# Sheet1.net
KiCad netlist of a schematic drawn in Altium Designer
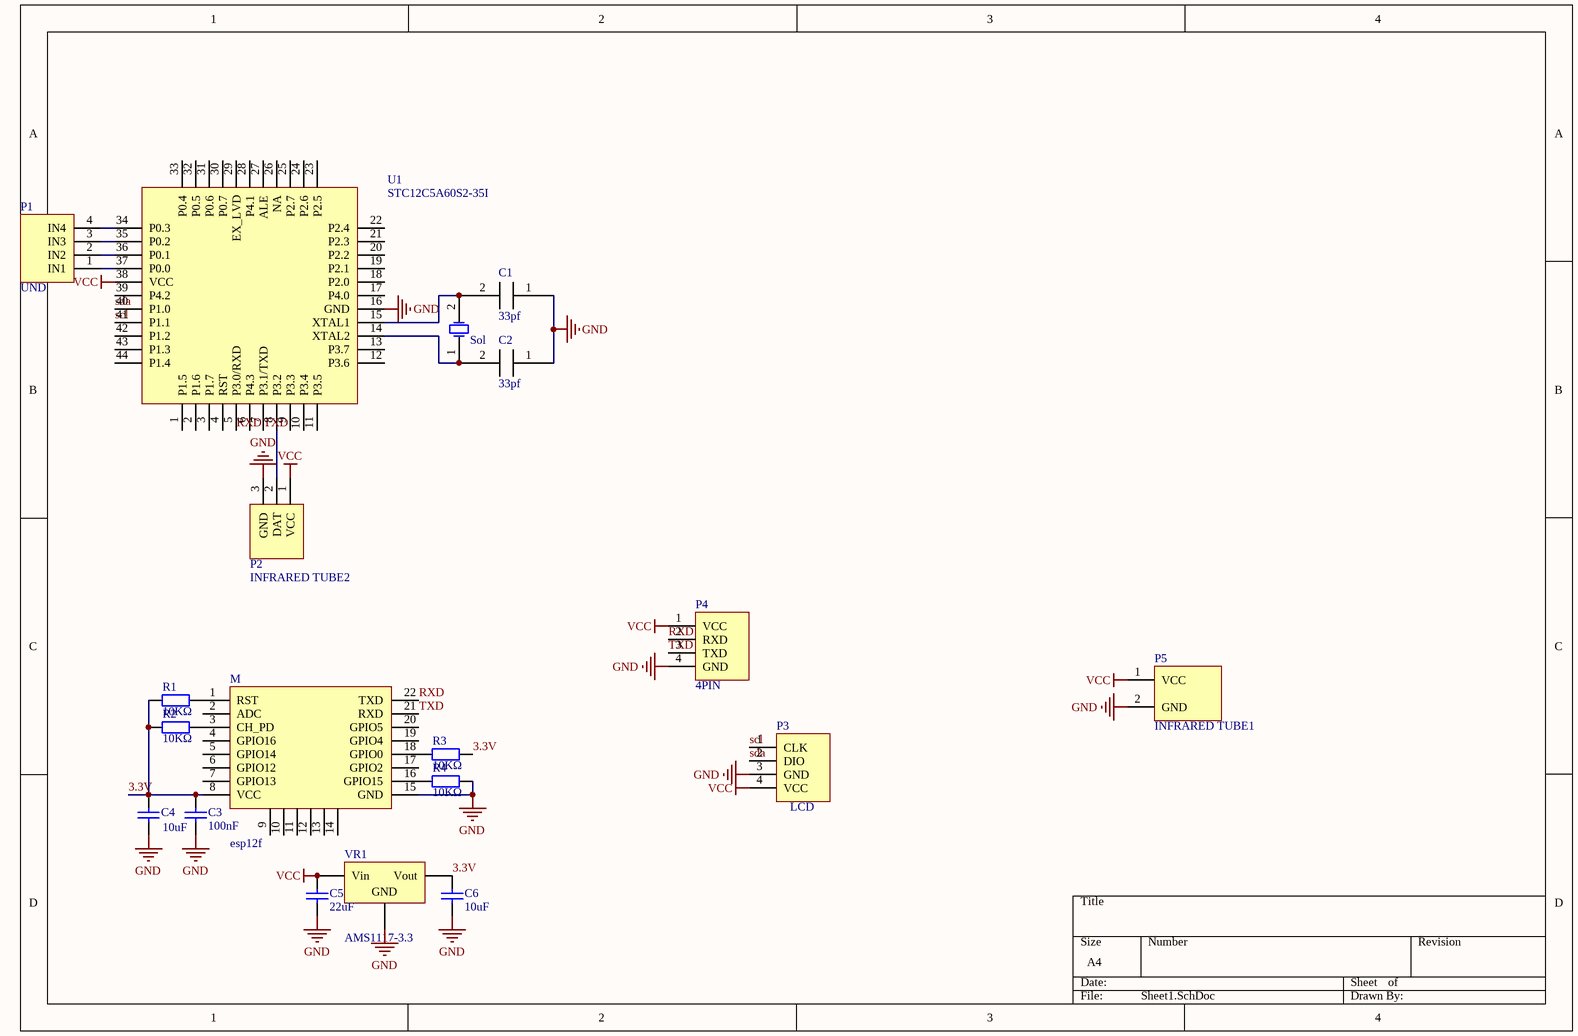
[diagram p0: Sheet1.SchDoc]

(export (version "E")
  (design (tool "Eeschema 10.0.6"))
  (components
    (comp (ref "C1")
      (value "33pf")
      (footprint "C 0805_M")
      (description "电容")
      (libsource (lib "Schlib1") (part "电容"))
    )
    (comp (ref "C2")
      (value "33pf")
      (footprint "C 0805_M")
      (description "电容")
      (libsource (lib "Schlib1") (part "电容"))
    )
    (comp (ref "C3")
      (value "100nF")
      (footprint "0805_C")
      (description "贴片电容")
      (libsource (lib "Cap") (part "0805 100nF(104) 10% 50V"))
    )
    (comp (ref "C4")
      (value "10uF")
      (footprint "0805_C")
      (description "贴片电容")
      (libsource (lib "Cap") (part "0805 10uF (106) 10% 25V"))
    )
    (comp (ref "C5")
      (value "22uF")
      (footprint "0805_C")
      (description "贴片电容")
      (libsource (lib "Cap") (part "0805 100nF(104) 10% 50V"))
    )
    (comp (ref "C6")
      (value "10uF")
      (footprint "0805_C")
      (description "贴片电容")
      (libsource (lib "Cap") (part "0805 100nF(104) 10% 50V"))
    )
    (comp (ref "M") (value "esp12f") (footprint "ESP_12E") (libsource (lib "Schlib1") (part "esp12f")))
    (comp (ref "P1") (value "UND") (footprint "HDR2.54-LI-4P") (libsource (lib "*") (part "4PIN UND")))
    (comp (ref "P2")
      (value "INFRARED TUBE2")
      (footprint "XH2.54-LI-3P")
      (libsource (lib "*") (part "INFRARED TUBE 2"))
    )
    (comp (ref "P3") (value "LCD") (footprint "HDR2.54-M-LI-4P") (libsource (lib "*") (part "lcd")))
    (comp (ref "P4") (value "4PIN") (footprint "HDR2.54-LI-4P") (libsource (lib "*") (part "4PIN")))
    (comp (ref "P5")
      (value "INFRARED TUBE1")
      (footprint "XH2.54-LI-2P")
      (libsource (lib "*") (part "INFRARED TUBE1"))
    )
    (comp (ref "R1")
      (value "10KΩ")
      (footprint "0805_R")
      (description "贴片电阻")
      (libsource (lib "RES") (part "0805 10KΩ (1002) 1%"))
    )
    (comp (ref "R2")
      (value "10KΩ")
      (footprint "0805_R")
      (description "贴片电阻")
      (libsource (lib "RES") (part "0805 10KΩ (1002) 1%"))
    )
    (comp (ref "R3")
      (value "10KΩ")
      (footprint "0805_R")
      (description "贴片电阻")
      (libsource (lib "RES") (part "0805 10KΩ (1002) 1%"))
    )
    (comp (ref "R4")
      (value "10KΩ")
      (footprint "0805_R")
      (description "贴片电阻")
      (libsource (lib "RES") (part "0805 10KΩ (1002) 1%"))
    )
    (comp (ref "Sol")
      (value "CrystalOscillator")
      (footprint "OSC HC-49S")
      (description "晶振")
      (libsource (lib "Schlib1") (part "XTAL"))
    )
    (comp (ref "U1")
      (value "STC12C5A60S2-35I")
      (footprint "LQFP-44_10x10x08P")
      (description "MCU")
      (libsource (lib "Schlib1") (part "STC12C5A60S2-35I"))
    )
    (comp (ref "VR1")
      (value "AMS1117-3.3")
      (footprint "SOT-223")
      (description "低压差线性稳压(LDO)")
      (libsource (lib "LDO") (part "SOT-223 AMS1117-3.3"))
    )
  )
  (nets
    (net (code "1") (name "/3.3V") (class "Default")
      (node (ref "C3") (pin "2") (pinfunction "2_2") (pintype "passive"))
      (node (ref "C4") (pin "2") (pinfunction "2_2") (pintype "passive"))
      (node (ref "C6") (pin "2") (pinfunction "2_2") (pintype "passive"))
      (node (ref "M") (pin "8") (pinfunction "VCC_8") (pintype "passive"))
      (node (ref "R1") (pin "1") (pinfunction "1_1") (pintype "passive"))
      (node (ref "R2") (pin "1") (pinfunction "1_1") (pintype "passive"))
      (node (ref "R3") (pin "2") (pinfunction "2_2") (pintype "passive"))
      (node (ref "VR1") (pin "2") (pinfunction "Vout_2") (pintype "passive"))
    )
    (net (code "2") (name "/RXD") (class "Default")
      (node (ref "M") (pin "22") (pinfunction "TXD_22") (pintype "passive"))
      (node (ref "P4") (pin "2") (pinfunction "RXD_2") (pintype "passive"))
      (node (ref "U1") (pin "5") (pinfunction "P3.0/RXD_5") (pintype "passive"))
    )
    (net (code "3") (name "/TXD") (class "Default")
      (node (ref "M") (pin "21") (pinfunction "RXD_21") (pintype "passive"))
      (node (ref "P4") (pin "3") (pinfunction "TXD_3") (pintype "passive"))
      (node (ref "U1") (pin "7") (pinfunction "P3.1/TXD_7") (pintype "passive"))
    )
    (net (code "4") (name "/scl") (class "Default")
      (node (ref "P3") (pin "1") (pinfunction "CLK_1") (pintype "passive"))
      (node (ref "U1") (pin "41") (pinfunction "P1.1_41") (pintype "passive"))
    )
    (net (code "5") (name "/sda") (class "Default")
      (node (ref "P3") (pin "2") (pinfunction "DIO_2") (pintype "passive"))
      (node (ref "U1") (pin "40") (pinfunction "P1.0_40") (pintype "passive"))
    )
    (net (code "6") (name "GND") (class "Default")
      (node (ref "C1") (pin "1") (pinfunction "1_1") (pintype "passive"))
      (node (ref "C2") (pin "1") (pinfunction "1_1") (pintype "passive"))
      (node (ref "C3") (pin "1") (pinfunction "1_1") (pintype "passive"))
      (node (ref "C4") (pin "1") (pinfunction "1_1") (pintype "passive"))
      (node (ref "C5") (pin "1") (pinfunction "1_1") (pintype "passive"))
      (node (ref "C6") (pin "1") (pinfunction "1_1") (pintype "passive"))
      (node (ref "M") (pin "15") (pinfunction "GND_15") (pintype "passive"))
      (node (ref "P2") (pin "3") (pinfunction "GND_3") (pintype "passive"))
      (node (ref "P3") (pin "3") (pinfunction "GND_3") (pintype "passive"))
      (node (ref "P4") (pin "4") (pinfunction "GND_4") (pintype "passive"))
      (node (ref "P5") (pin "2") (pinfunction "GND_2") (pintype "passive"))
      (node (ref "R4") (pin "2") (pinfunction "2_2") (pintype "passive"))
      (node (ref "U1") (pin "16") (pinfunction "GND_16") (pintype "power_in"))
      (node (ref "VR1") (pin "1") (pinfunction "GND_1") (pintype "passive"))
    )
    (net (code "7") (name "Net-(M-CH_PD)") (class "Default")
      (node (ref "M") (pin "3") (pinfunction "CH_PD_3") (pintype "passive"))
      (node (ref "R2") (pin "2") (pinfunction "2_2") (pintype "passive"))
    )
    (net (code "8") (name "Net-(M-GPIO0)") (class "Default")
      (node (ref "M") (pin "18") (pinfunction "GPIO0_18") (pintype "passive"))
      (node (ref "R3") (pin "1") (pinfunction "1_1") (pintype "passive"))
    )
    (net (code "9") (name "Net-(M-GPIO15)") (class "Default")
      (node (ref "M") (pin "16") (pinfunction "GPIO15_16") (pintype "passive"))
      (node (ref "R4") (pin "1") (pinfunction "1_1") (pintype "passive"))
    )
    (net (code "10") (name "Net-(M-RST)") (class "Default")
      (node (ref "M") (pin "1") (pinfunction "RST_1") (pintype "passive"))
      (node (ref "R1") (pin "2") (pinfunction "2_2") (pintype "passive"))
    )
    (net (code "11") (name "Net-(P1-IN1)") (class "Default")
      (node (ref "P1") (pin "1") (pinfunction "IN1_1") (pintype "passive"))
      (node (ref "U1") (pin "37") (pinfunction "P0.0_37") (pintype "passive"))
    )
    (net (code "12") (name "Net-(P1-IN2)") (class "Default")
      (node (ref "P1") (pin "2") (pinfunction "IN2_2") (pintype "passive"))
      (node (ref "U1") (pin "36") (pinfunction "P0.1_36") (pintype "passive"))
    )
    (net (code "13") (name "Net-(P1-IN3)") (class "Default")
      (node (ref "P1") (pin "3") (pinfunction "IN3_3") (pintype "passive"))
      (node (ref "U1") (pin "35") (pinfunction "P0.2_35") (pintype "passive"))
    )
    (net (code "14") (name "Net-(P1-IN4)") (class "Default")
      (node (ref "P1") (pin "4") (pinfunction "IN4_4") (pintype "passive"))
      (node (ref "U1") (pin "34") (pinfunction "P0.3_34") (pintype "passive"))
    )
    (net (code "15") (name "Net-(P2-DAT)") (class "Default")
      (node (ref "P2") (pin "2") (pinfunction "DAT_2") (pintype "passive"))
      (node (ref "U1") (pin "8") (pinfunction "P3.2_8") (pintype "passive"))
    )
    (net (code "16") (name "Net-(Sol-OSC1)") (class "Default")
      (node (ref "C2") (pin "2") (pinfunction "2_2") (pintype "passive"))
      (node (ref "Sol") (pin "1") (pinfunction "OSC1_1") (pintype "passive"))
      (node (ref "U1") (pin "14") (pinfunction "XTAL2_14") (pintype "passive"))
    )
    (net (code "17") (name "Net-(Sol-OSC2)") (class "Default")
      (node (ref "C1") (pin "2") (pinfunction "2_2") (pintype "passive"))
      (node (ref "Sol") (pin "2") (pinfunction "OSC2_2") (pintype "passive"))
      (node (ref "U1") (pin "15") (pinfunction "XTAL1_15") (pintype "passive"))
    )
    (net (code "18") (name "VCC") (class "Default")
      (node (ref "C5") (pin "2") (pinfunction "2_2") (pintype "passive"))
      (node (ref "P2") (pin "1") (pinfunction "VCC_1") (pintype "passive"))
      (node (ref "P3") (pin "4") (pinfunction "VCC_4") (pintype "passive"))
      (node (ref "P4") (pin "1") (pinfunction "VCC_1") (pintype "passive"))
      (node (ref "P5") (pin "1") (pinfunction "VCC_1") (pintype "passive"))
      (node (ref "U1") (pin "38") (pinfunction "VCC_38") (pintype "power_in"))
      (node (ref "VR1") (pin "3") (pinfunction "Vin_3") (pintype "passive"))
    )
    (net (code "19") (name "unconnected-(M-ADC-Pad2)") (class "Default")
      (node (ref "M") (pin "2") (pinfunction "ADC_2") (pintype "passive"))
    )
    (net (code "20") (name "unconnected-(M-GPIO2-Pad17)") (class "Default")
      (node (ref "M") (pin "17") (pinfunction "GPIO2_17") (pintype "passive"))
    )
    (net (code "21") (name "unconnected-(M-GPIO4-Pad19)") (class "Default")
      (node (ref "M") (pin "19") (pinfunction "GPIO4_19") (pintype "passive"))
    )
    (net (code "22") (name "unconnected-(M-GPIO5-Pad20)") (class "Default")
      (node (ref "M") (pin "20") (pinfunction "GPIO5_20") (pintype "passive"))
    )
    (net (code "23") (name "unconnected-(M-GPIO12-Pad6)") (class "Default")
      (node (ref "M") (pin "6") (pinfunction "GPIO12_6") (pintype "passive"))
    )
    (net (code "24") (name "unconnected-(M-GPIO13-Pad7)") (class "Default")
      (node (ref "M") (pin "7") (pinfunction "GPIO13_7") (pintype "passive"))
    )
    (net (code "25") (name "unconnected-(M-GPIO14-Pad5)") (class "Default")
      (node (ref "M") (pin "5") (pinfunction "GPIO14_5") (pintype "passive"))
    )
    (net (code "26") (name "unconnected-(M-GPIO16-Pad4)") (class "Default")
      (node (ref "M") (pin "4") (pinfunction "GPIO16_4") (pintype "passive"))
    )
    (net (code "27") (name "unconnected-(M-Pad9)") (class "Default")
      (node (ref "M") (pin "9") (pintype "passive"))
    )
    (net (code "28") (name "unconnected-(M-Pad10)") (class "Default")
      (node (ref "M") (pin "10") (pintype "passive"))
    )
    (net (code "29") (name "unconnected-(M-Pad11)") (class "Default")
      (node (ref "M") (pin "11") (pintype "passive"))
    )
    (net (code "30") (name "unconnected-(M-Pad12)") (class "Default")
      (node (ref "M") (pin "12") (pintype "passive"))
    )
    (net (code "31") (name "unconnected-(M-Pad13)") (class "Default")
      (node (ref "M") (pin "13") (pintype "passive"))
    )
    (net (code "32") (name "unconnected-(M-Pad14)") (class "Default")
      (node (ref "M") (pin "14") (pintype "passive"))
    )
    (net (code "33") (name "unconnected-(U1-ALE-Pad27)") (class "Default")
      (node (ref "U1") (pin "27") (pinfunction "ALE_27") (pintype "passive"))
    )
    (net (code "34") (name "unconnected-(U1-EX_LVD-Pad29)") (class "Default")
      (node (ref "U1") (pin "29") (pinfunction "EX_LVD_29") (pintype "passive"))
    )
    (net (code "35") (name "unconnected-(U1-NA-Pad26)") (class "Default")
      (node (ref "U1") (pin "26") (pinfunction "NA_26") (pintype "passive"))
    )
    (net (code "36") (name "unconnected-(U1-P0.4-Pad33)") (class "Default")
      (node (ref "U1") (pin "33") (pinfunction "P0.4_33") (pintype "passive"))
    )
    (net (code "37") (name "unconnected-(U1-P0.5-Pad32)") (class "Default")
      (node (ref "U1") (pin "32") (pinfunction "P0.5_32") (pintype "passive"))
    )
    (net (code "38") (name "unconnected-(U1-P0.6-Pad31)") (class "Default")
      (node (ref "U1") (pin "31") (pinfunction "P0.6_31") (pintype "passive"))
    )
    (net (code "39") (name "unconnected-(U1-P0.7-Pad30)") (class "Default")
      (node (ref "U1") (pin "30") (pinfunction "P0.7_30") (pintype "passive"))
    )
    (net (code "40") (name "unconnected-(U1-P1.2-Pad42)") (class "Default")
      (node (ref "U1") (pin "42") (pinfunction "P1.2_42") (pintype "passive"))
    )
    (net (code "41") (name "unconnected-(U1-P1.3-Pad43)") (class "Default")
      (node (ref "U1") (pin "43") (pinfunction "P1.3_43") (pintype "passive"))
    )
    (net (code "42") (name "unconnected-(U1-P1.4-Pad44)") (class "Default")
      (node (ref "U1") (pin "44") (pinfunction "P1.4_44") (pintype "passive"))
    )
    (net (code "43") (name "unconnected-(U1-P1.5-Pad1)") (class "Default")
      (node (ref "U1") (pin "1") (pinfunction "P1.5_1") (pintype "passive"))
    )
    (net (code "44") (name "unconnected-(U1-P1.6-Pad2)") (class "Default")
      (node (ref "U1") (pin "2") (pinfunction "P1.6_2") (pintype "passive"))
    )
    (net (code "45") (name "unconnected-(U1-P1.7-Pad3)") (class "Default")
      (node (ref "U1") (pin "3") (pinfunction "P1.7_3") (pintype "passive"))
    )
    (net (code "46") (name "unconnected-(U1-P2.0-Pad18)") (class "Default")
      (node (ref "U1") (pin "18") (pinfunction "P2.0_18") (pintype "passive"))
    )
    (net (code "47") (name "unconnected-(U1-P2.1-Pad19)") (class "Default")
      (node (ref "U1") (pin "19") (pinfunction "P2.1_19") (pintype "passive"))
    )
    (net (code "48") (name "unconnected-(U1-P2.2-Pad20)") (class "Default")
      (node (ref "U1") (pin "20") (pinfunction "P2.2_20") (pintype "passive"))
    )
    (net (code "49") (name "unconnected-(U1-P2.3-Pad21)") (class "Default")
      (node (ref "U1") (pin "21") (pinfunction "P2.3_21") (pintype "passive"))
    )
    (net (code "50") (name "unconnected-(U1-P2.4-Pad22)") (class "Default")
      (node (ref "U1") (pin "22") (pinfunction "P2.4_22") (pintype "passive"))
    )
    (net (code "51") (name "unconnected-(U1-P2.5-Pad23)") (class "Default")
      (node (ref "U1") (pin "23") (pinfunction "P2.5_23") (pintype "passive"))
    )
    (net (code "52") (name "unconnected-(U1-P2.6-Pad24)") (class "Default")
      (node (ref "U1") (pin "24") (pinfunction "P2.6_24") (pintype "passive"))
    )
    (net (code "53") (name "unconnected-(U1-P2.7-Pad25)") (class "Default")
      (node (ref "U1") (pin "25") (pinfunction "P2.7_25") (pintype "passive"))
    )
    (net (code "54") (name "unconnected-(U1-P3.3-Pad9)") (class "Default")
      (node (ref "U1") (pin "9") (pinfunction "P3.3_9") (pintype "passive"))
    )
    (net (code "55") (name "unconnected-(U1-P3.4-Pad10)") (class "Default")
      (node (ref "U1") (pin "10") (pinfunction "P3.4_10") (pintype "passive"))
    )
    (net (code "56") (name "unconnected-(U1-P3.5-Pad11)") (class "Default")
      (node (ref "U1") (pin "11") (pinfunction "P3.5_11") (pintype "passive"))
    )
    (net (code "57") (name "unconnected-(U1-P3.6-Pad12)") (class "Default")
      (node (ref "U1") (pin "12") (pinfunction "P3.6_12") (pintype "passive"))
    )
    (net (code "58") (name "unconnected-(U1-P3.7-Pad13)") (class "Default")
      (node (ref "U1") (pin "13") (pinfunction "P3.7_13") (pintype "passive"))
    )
    (net (code "59") (name "unconnected-(U1-P4.0-Pad17)") (class "Default")
      (node (ref "U1") (pin "17") (pinfunction "P4.0_17") (pintype "passive"))
    )
    (net (code "60") (name "unconnected-(U1-P4.1-Pad28)") (class "Default")
      (node (ref "U1") (pin "28") (pinfunction "P4.1_28") (pintype "passive"))
    )
    (net (code "61") (name "unconnected-(U1-P4.2-Pad39)") (class "Default")
      (node (ref "U1") (pin "39") (pinfunction "P4.2_39") (pintype "passive"))
    )
    (net (code "62") (name "unconnected-(U1-P4.3-Pad6)") (class "Default")
      (node (ref "U1") (pin "6") (pinfunction "P4.3_6") (pintype "passive"))
    )
    (net (code "63") (name "unconnected-(U1-RST-Pad4)") (class "Default")
      (node (ref "U1") (pin "4") (pinfunction "RST_4") (pintype "passive"))
    )
  )
)
